# H2BR00.net
KiCad netlist of a schematic drawn in EAGLE
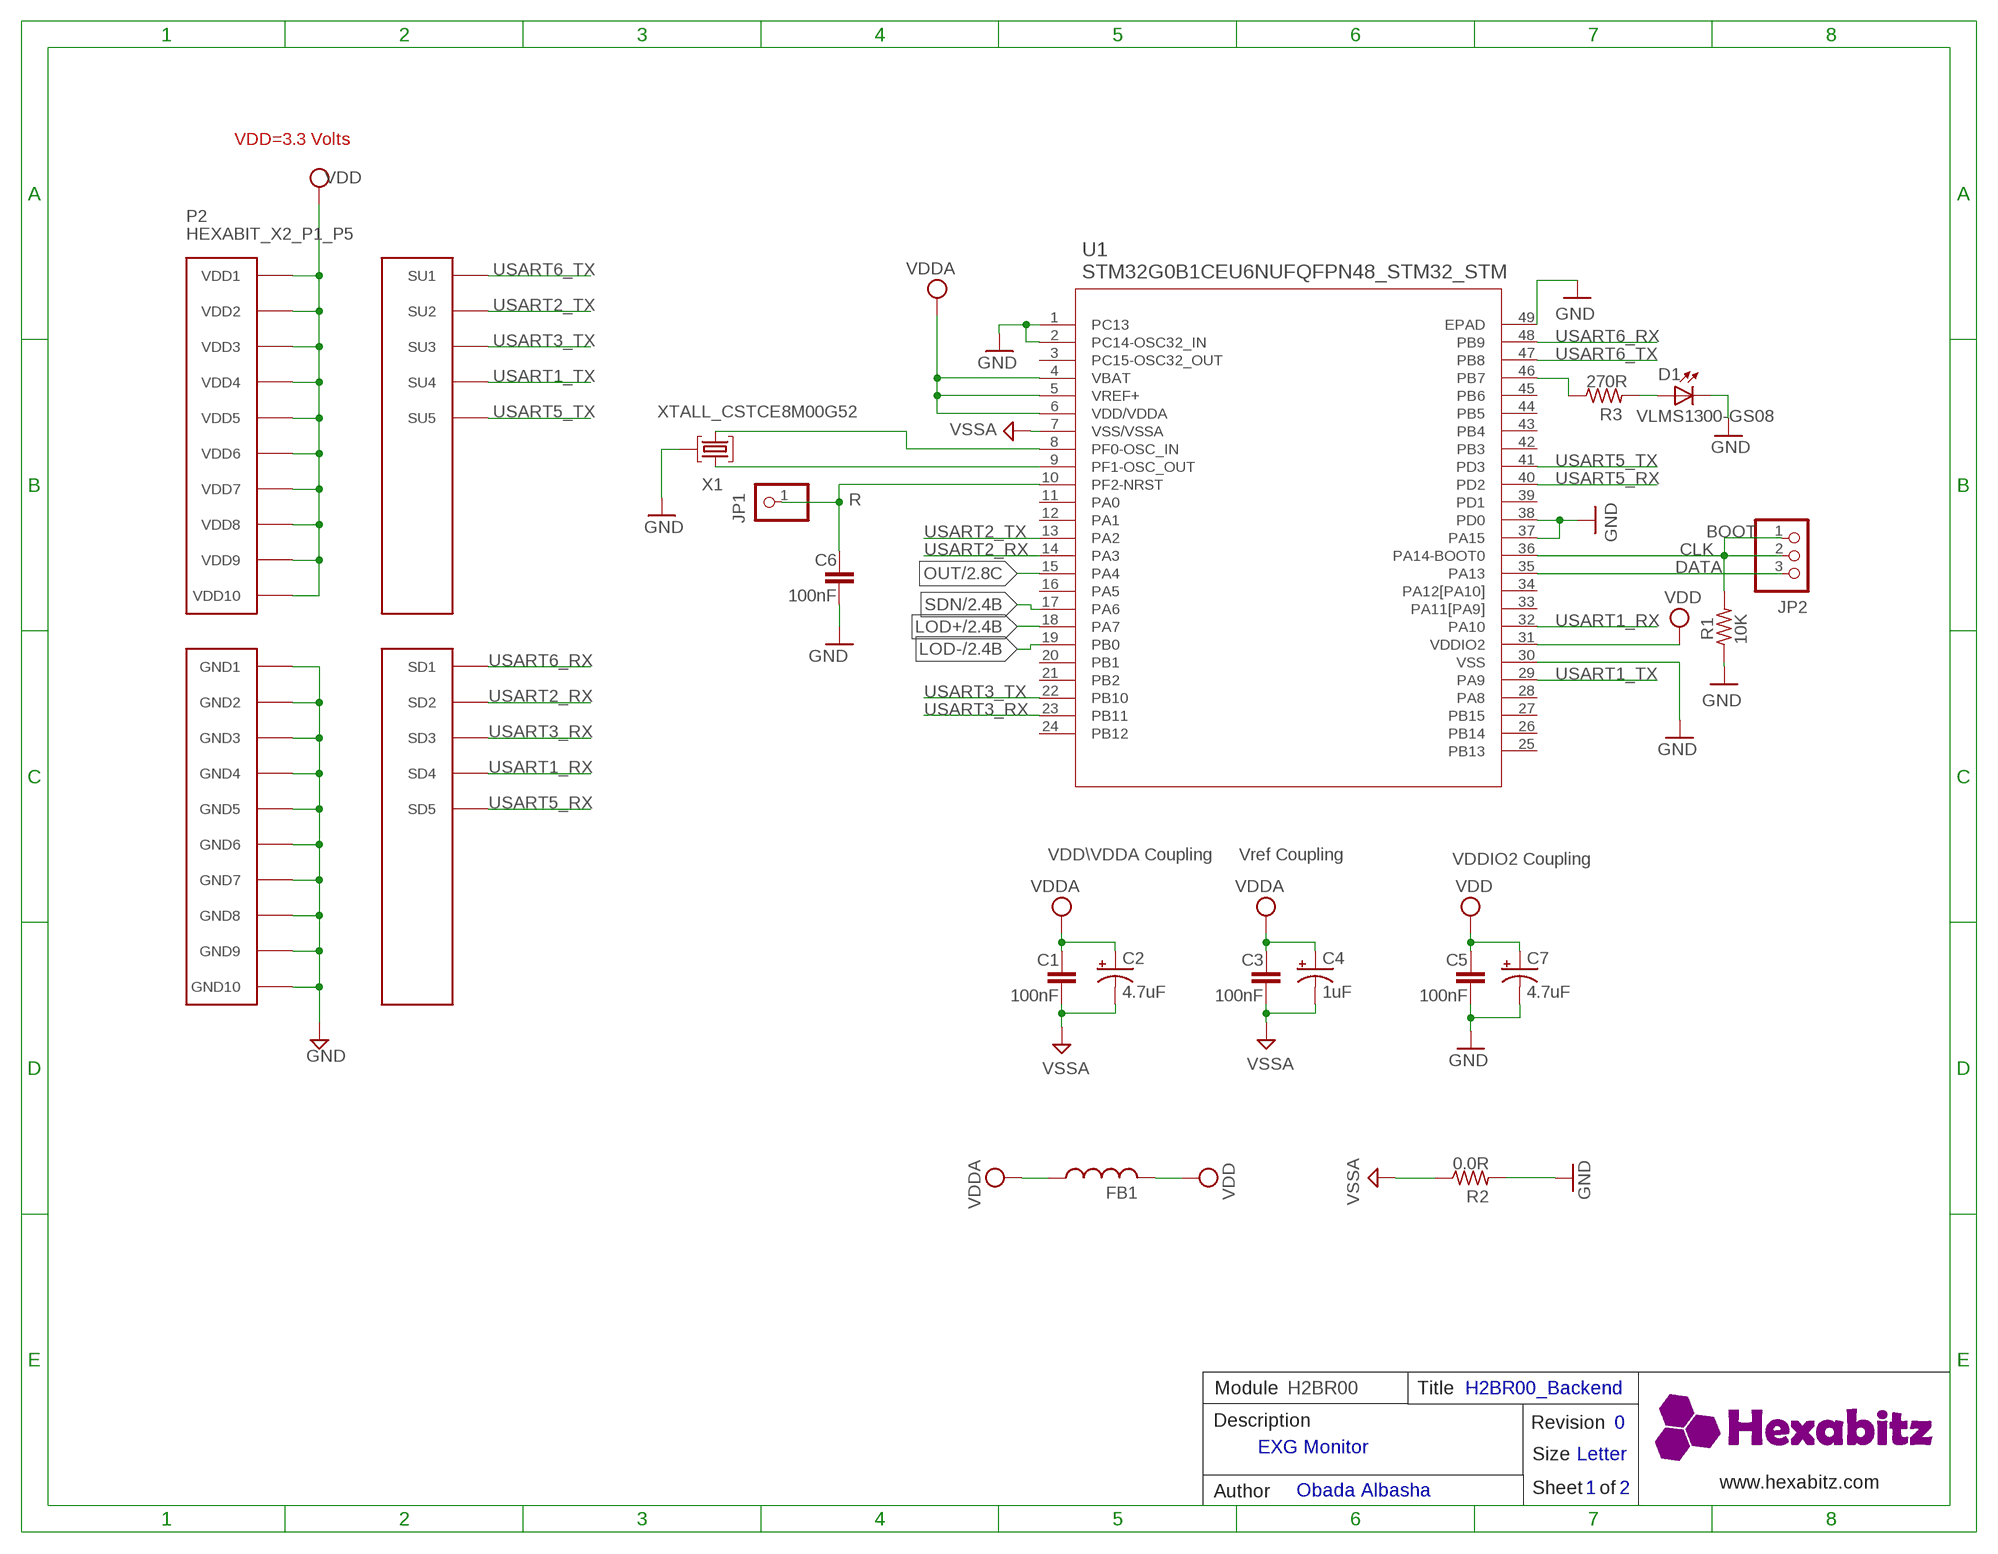
[diagram p0: schematic, sheet 1]
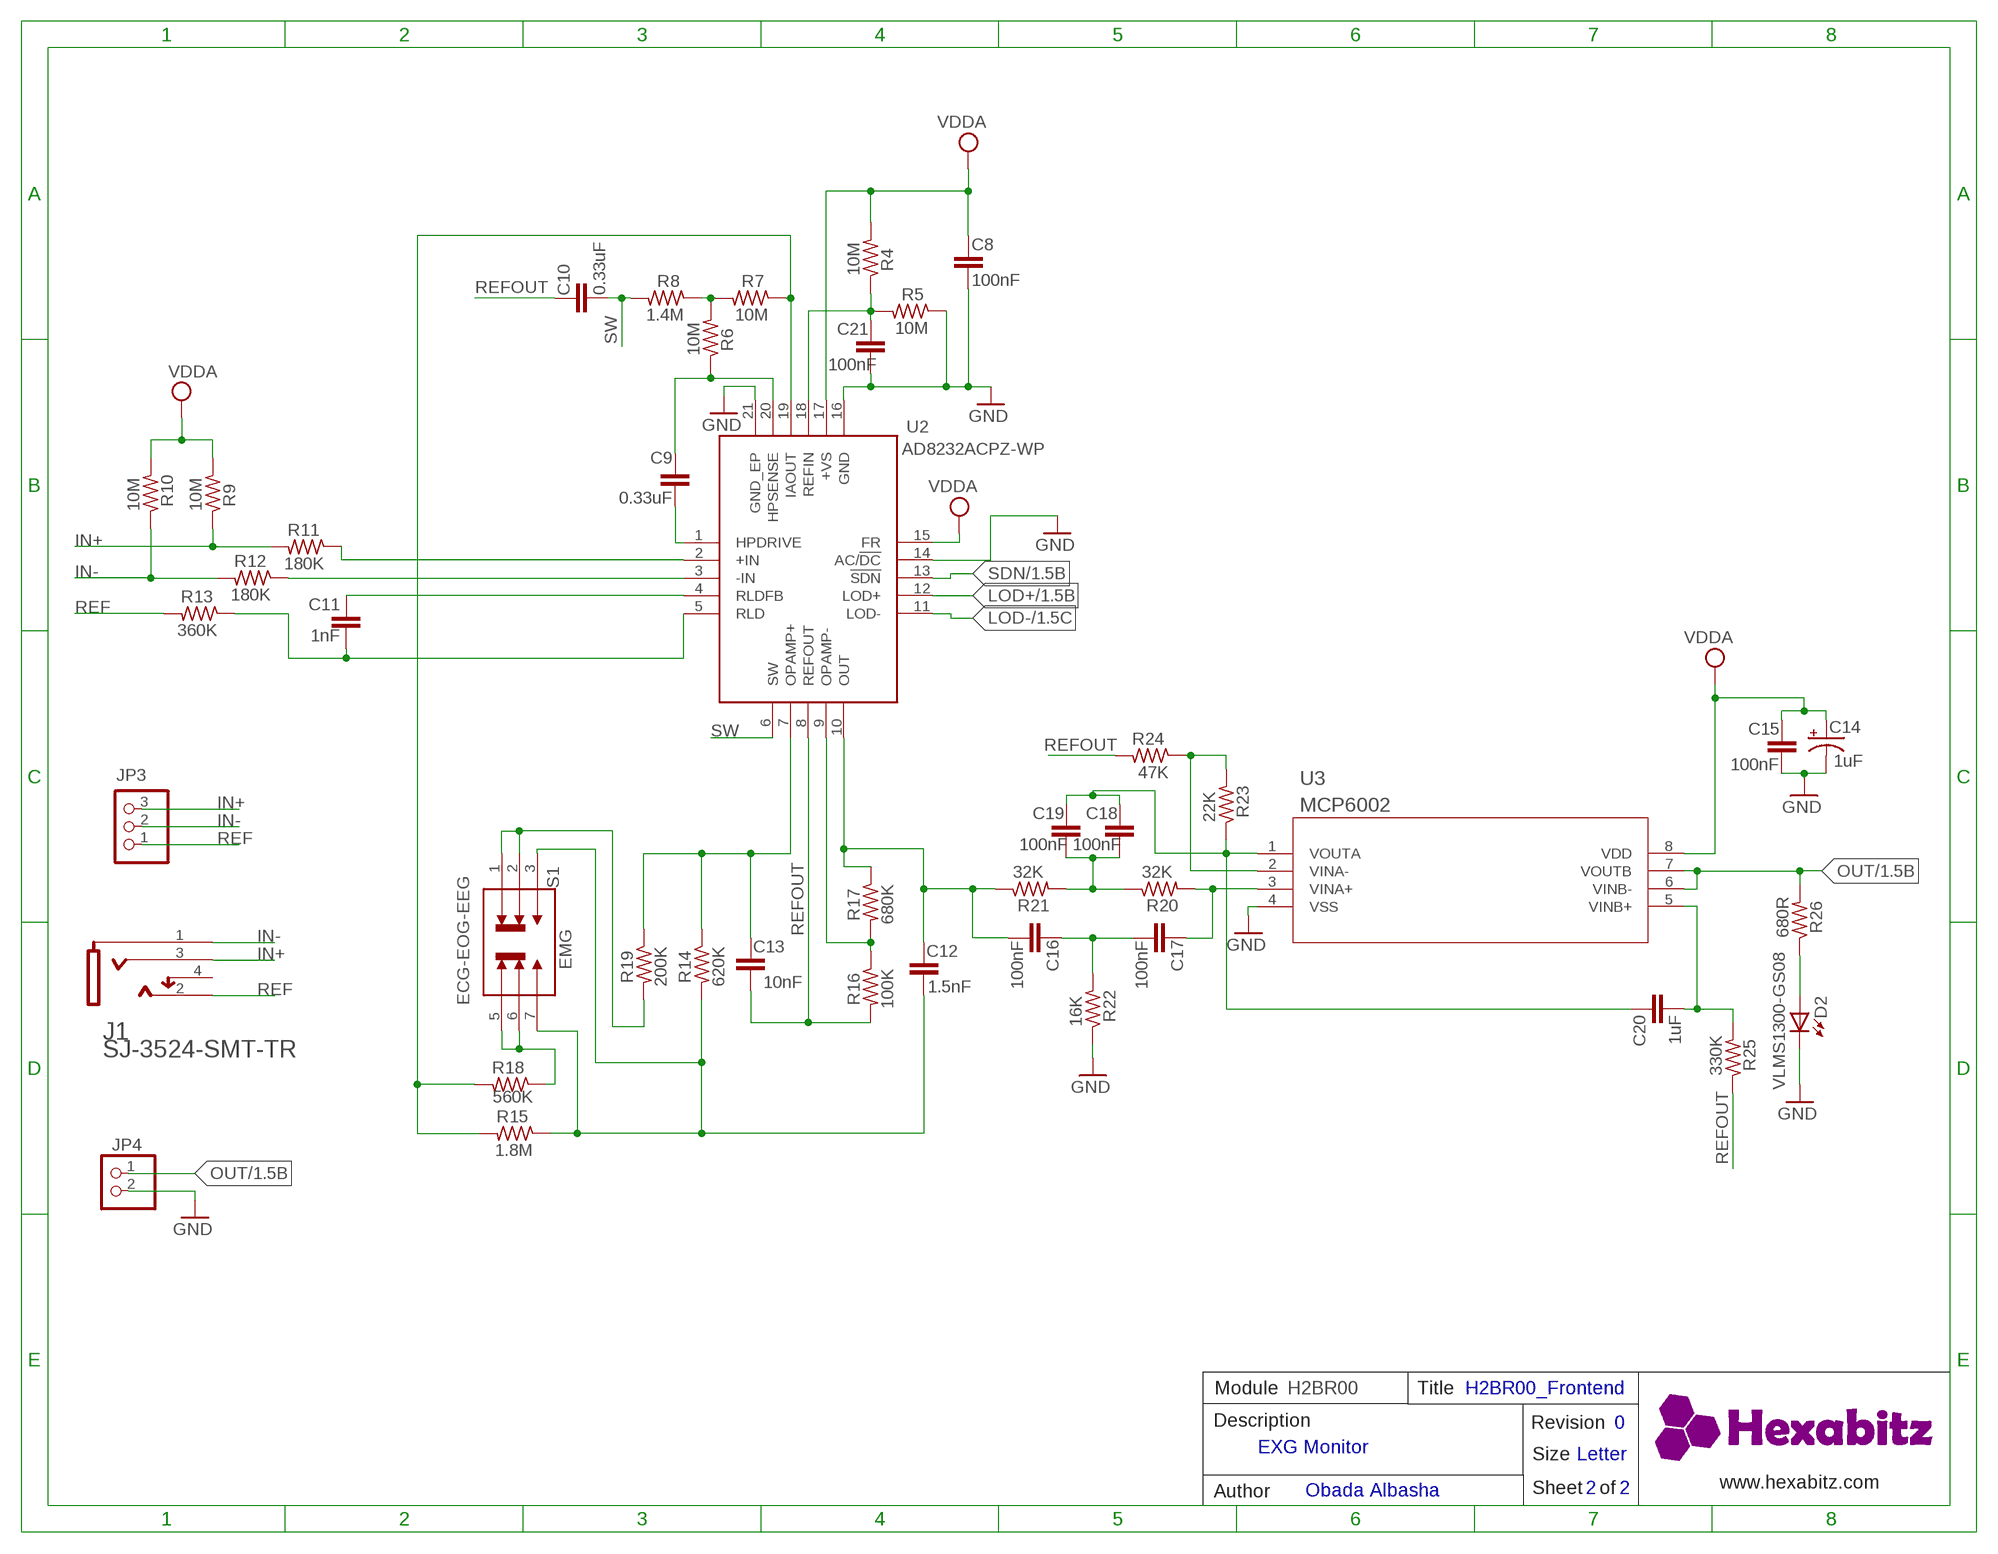
[diagram p1: schematic, sheet 2]

(export (version "E")
  (design (tool "Eeschema 10.0.6"))
  (components
    (comp (ref "C8")
      (value "100nF")
      (footprint "eagle-import:C-0603")
      (libsource (lib "eagle-import") (part "C-0603"))
    )
    (comp (ref "C9")
      (value "0.33uF")
      (footprint "eagle-import:C-0603")
      (libsource (lib "eagle-import") (part "C-0603"))
    )
    (comp (ref "C10")
      (value "0.33uF")
      (footprint "eagle-import:C-0603")
      (libsource (lib "eagle-import") (part "C-0603"))
    )
    (comp (ref "C11")
      (value "1nF")
      (footprint "eagle-import:C-0603")
      (libsource (lib "eagle-import") (part "C-0603"))
    )
    (comp (ref "C12")
      (value "1.5nF")
      (footprint "eagle-import:C-0603")
      (libsource (lib "eagle-import") (part "C-0603"))
    )
    (comp (ref "C13")
      (value "10nF")
      (footprint "eagle-import:C-0603")
      (libsource (lib "eagle-import") (part "C-0603"))
    )
    (comp (ref "C14")
      (value "1uF")
      (footprint "eagle-import:C-0805-POL")
      (libsource (lib "eagle-import") (part "C-0805-POL"))
    )
    (comp (ref "C15")
      (value "100nF")
      (footprint "eagle-import:C-0603")
      (libsource (lib "eagle-import") (part "C-0603"))
    )
    (comp (ref "C16")
      (value "100nF")
      (footprint "eagle-import:C-0603")
      (libsource (lib "eagle-import") (part "C-0603"))
    )
    (comp (ref "C17")
      (value "100nF")
      (footprint "eagle-import:C-0603")
      (libsource (lib "eagle-import") (part "C-0603"))
    )
    (comp (ref "C18")
      (value "100nF")
      (footprint "eagle-import:C-0603")
      (libsource (lib "eagle-import") (part "C-0603"))
    )
    (comp (ref "C19")
      (value "100nF")
      (footprint "eagle-import:C-0603")
      (libsource (lib "eagle-import") (part "C-0603"))
    )
    (comp (ref "C20")
      (value "1uF")
      (footprint "eagle-import:C-0603")
      (libsource (lib "eagle-import") (part "C-0603"))
    )
    (comp (ref "C21")
      (value "100nF")
      (footprint "eagle-import:C-0603")
      (libsource (lib "eagle-import") (part "C-0603"))
    )
    (comp (ref "D2")
      (value "VLMS1300-GS08")
      (footprint "eagle-import:VLMS1300-GS08")
      (fields
        (field (name "MFN") "Vishay")
        (field (name "MPN") "VLMS1300-GS08")
        (field (name "OCTOPART_URL") "https://octopart.com/vlms1300-gs08-vishay-21709201?r=sp&s=_gcP4_q8T1SC6PJQPTQ9yA")
      )
      (libsource (lib "eagle-import") (part "VLMS1300-GS08"))
    )
    (comp (ref "J1")
      (value "CUI_DEVICES_SJ-3524-SMT-TRCUI_DEVICES_SJ-3524-SMT-TR_0_0")
      (footprint "eagle-import:CUI_DEVICES_SJ-3524-SMT-TR_0")
      (fields
        (field (name "DIGIKEY_PART_NUMBER") "CP-3524SJCT-ND")
        (field (name "MOUSER_PART_NUMBER") "490-SJ-3524-SMT-TR")
        (field (name "MPN") "SJ-3524-SMT-TR")
      )
      (libsource (lib "eagle-import") (part "CUI_DEVICES_SJ-3524-SMT-TRCUI_DEVICES_SJ-3524-SMT-TR_0_0"))
    )
    (comp (ref "JP3")
      (value "PINHD-1X3")
      (footprint "eagle-import:1X03")
      (libsource (lib "eagle-import") (part "PINHD-1X3"))
    )
    (comp (ref "JP4")
      (value "PINHD-1X2(ROUND)")
      (footprint "eagle-import:1X02")
      (libsource (lib "eagle-import") (part "PINHD-1X2(ROUND)"))
    )
    (comp (ref "R4")
      (value "10M")
      (footprint "eagle-import:R-0603")
      (libsource (lib "eagle-import") (part "R-0603"))
    )
    (comp (ref "R5")
      (value "10M")
      (footprint "eagle-import:R-0603")
      (libsource (lib "eagle-import") (part "R-0603"))
    )
    (comp (ref "R6")
      (value "10M")
      (footprint "eagle-import:R-0603")
      (libsource (lib "eagle-import") (part "R-0603"))
    )
    (comp (ref "R7")
      (value "10M")
      (footprint "eagle-import:R-0603")
      (libsource (lib "eagle-import") (part "R-0603"))
    )
    (comp (ref "R8")
      (value "1.4M")
      (footprint "eagle-import:R-0603")
      (libsource (lib "eagle-import") (part "R-0603"))
    )
    (comp (ref "R9")
      (value "10M")
      (footprint "eagle-import:R-0603")
      (libsource (lib "eagle-import") (part "R-0603"))
    )
    (comp (ref "R10")
      (value "10M")
      (footprint "eagle-import:R-0603")
      (libsource (lib "eagle-import") (part "R-0603"))
    )
    (comp (ref "R11")
      (value "180K")
      (footprint "eagle-import:R-0603")
      (libsource (lib "eagle-import") (part "R-0603"))
    )
    (comp (ref "R12")
      (value "180K")
      (footprint "eagle-import:R-0603")
      (libsource (lib "eagle-import") (part "R-0603"))
    )
    (comp (ref "R13")
      (value "360K")
      (footprint "eagle-import:R-0603")
      (libsource (lib "eagle-import") (part "R-0603"))
    )
    (comp (ref "R14")
      (value "620K")
      (footprint "eagle-import:R-0603")
      (libsource (lib "eagle-import") (part "R-0603"))
    )
    (comp (ref "R15")
      (value "1.8M")
      (footprint "eagle-import:R-0603")
      (libsource (lib "eagle-import") (part "R-0603"))
    )
    (comp (ref "R16")
      (value "100K")
      (footprint "eagle-import:R-0603")
      (libsource (lib "eagle-import") (part "R-0603"))
    )
    (comp (ref "R17")
      (value "680K")
      (footprint "eagle-import:R-0603")
      (libsource (lib "eagle-import") (part "R-0603"))
    )
    (comp (ref "R18")
      (value "560K")
      (footprint "eagle-import:R-0603")
      (libsource (lib "eagle-import") (part "R-0603"))
    )
    (comp (ref "R19")
      (value "200K")
      (footprint "eagle-import:R-0603")
      (libsource (lib "eagle-import") (part "R-0603"))
    )
    (comp (ref "R20")
      (value "32K")
      (footprint "eagle-import:R-0603")
      (libsource (lib "eagle-import") (part "R-0603"))
    )
    (comp (ref "R21")
      (value "32K")
      (footprint "eagle-import:R-0603")
      (libsource (lib "eagle-import") (part "R-0603"))
    )
    (comp (ref "R22")
      (value "16K")
      (footprint "eagle-import:R-0603")
      (libsource (lib "eagle-import") (part "R-0603"))
    )
    (comp (ref "R23")
      (value "22K")
      (footprint "eagle-import:R-0603")
      (libsource (lib "eagle-import") (part "R-0603"))
    )
    (comp (ref "R24")
      (value "47K")
      (footprint "eagle-import:R-0603")
      (libsource (lib "eagle-import") (part "R-0603"))
    )
    (comp (ref "R25")
      (value "330K")
      (footprint "eagle-import:R-0603")
      (libsource (lib "eagle-import") (part "R-0603"))
    )
    (comp (ref "R26")
      (value "680R")
      (footprint "eagle-import:R-0603")
      (libsource (lib "eagle-import") (part "R-0603"))
    )
    (comp (ref "S1")
      (value "JS202011JCQN")
      (footprint "eagle-import:SW_JS202011JCQN")
      (fields (field (name "DIGI-KEY_PART_NUMBER") "CKN10723TR-ND") (field (name "MF") "C&K"))
      (libsource (lib "eagle-import") (part "JS202011JCQN"))
    )
    (comp (ref "U2")
      (value "AD8232ACPZ-WP")
      (footprint "eagle-import:QFN50P400X400X80-21N")
      (fields (field (name "MOUSER_PART_NUMBER") "584-AD8232ACPZ-WP"))
      (libsource (lib "eagle-import") (part "AD8232ACPZ-WP"))
    )
    (comp (ref "U3")
      (value "MCP6002")
      (footprint "eagle-import:SOIC8-N_MC_MCH-L")
      (fields
        (field (name "MANUFACTURER_PART_NUMBER") "MCP6002-I/SN")
        (field (name "COPYRIGHT") "Copyright (C) 2022 Ultra Librarian. All rights reserved.")
      )
      (libsource (lib "eagle-import") (part "MCP6002-I/SNSOIC8-N_MC_MCH-L"))
    )
    (comp (ref "C1")
      (value "100nF")
      (footprint "eagle-import:C-0603")
      (libsource (lib "eagle-import") (part "C-0603"))
    )
    (comp (ref "C2")
      (value "4.7uF")
      (footprint "eagle-import:C-0805-POL")
      (libsource (lib "eagle-import") (part "C-0805-POL"))
    )
    (comp (ref "C3")
      (value "100nF")
      (footprint "eagle-import:C-0603")
      (libsource (lib "eagle-import") (part "C-0603"))
    )
    (comp (ref "C4")
      (value "1uF")
      (footprint "eagle-import:C-0805-POL")
      (libsource (lib "eagle-import") (part "C-0805-POL"))
    )
    (comp (ref "C5")
      (value "100nF")
      (footprint "eagle-import:C-0603")
      (libsource (lib "eagle-import") (part "C-0603"))
    )
    (comp (ref "C6")
      (value "100nF")
      (footprint "eagle-import:C-0603")
      (libsource (lib "eagle-import") (part "C-0603"))
    )
    (comp (ref "C7")
      (value "4.7uF")
      (footprint "eagle-import:C-0805-POL")
      (libsource (lib "eagle-import") (part "C-0805-POL"))
    )
    (comp (ref "D1")
      (value "VLMS1300-GS08")
      (footprint "eagle-import:VLMS1300-GS08")
      (fields
        (field (name "MFN") "Vishay")
        (field (name "MPN") "VLMS1300-GS08")
        (field (name "OCTOPART_URL") "https://octopart.com/vlms1300-gs08-vishay-21709201?r=sp&s=_gcP4_q8T1SC6PJQPTQ9yA")
      )
      (libsource (lib "eagle-import") (part "VLMS1300-GS08"))
    )
    (comp (ref "FB1")
      (value "FB-0603")
      (footprint "eagle-import:FB-0603")
      (libsource (lib "eagle-import") (part "FB-0603"))
    )
    (comp (ref "JP1")
      (value "R")
      (footprint "eagle-import:1X01")
      (fields (field (name "MPN") "87227-1"))
      (libsource (lib "eagle-import") (part "PINHD-1X1"))
    )
    (comp (ref "JP2")
      (value "PINHD-1X3")
      (footprint "eagle-import:1X03")
      (libsource (lib "eagle-import") (part "PINHD-1X3"))
    )
    (comp (ref "P2")
      (value "HEXABIT_X2_P1_P5")
      (footprint "eagle-import:HEXABIT_17.32_X2_P1_P5")
      (libsource (lib "eagle-import") (part "HEXABIT_X2_P1_P5"))
    )
    (comp (ref "R1")
      (value "10K")
      (footprint "eagle-import:R-0603")
      (libsource (lib "eagle-import") (part "R-0603"))
    )
    (comp (ref "R2")
      (value "0.0R")
      (footprint "eagle-import:R-0603")
      (libsource (lib "eagle-import") (part "R-0603"))
    )
    (comp (ref "R3")
      (value "270R")
      (footprint "eagle-import:R-0603")
      (libsource (lib "eagle-import") (part "R-0603"))
    )
    (comp (ref "U1")
      (value "STM32G0B1CEU6NUFQFPN48_STM32_STM")
      (footprint "eagle-import:UFQFPN48_STM32_STM")
      (fields
        (field (name "MPN") "STM32G0B1CEU6N")
        (field (name "COPYRIGHT") "Copyright (C) 2022 Ultra Librarian. All rights reserved.")
      )
      (libsource (lib "eagle-import") (part "STM32G0B1CEU6NUFQFPN48_STM32_STM"))
    )
    (comp (ref "X1")
      (value "XTALL_CSTCE8M00G52")
      (footprint "eagle-import:XTALL_CSTCE8M00G52")
      (fields (field (name "MPN") "CSTCE8M00G52Z-R0"))
      (libsource (lib "eagle-import") (part "XTALL_CSTCE8M00G52"))
    )
  )
  (nets
    (net (code "1") (name "CLK") (class "Default")
      (node (ref "JP2") (pin "1") (pinfunction "1_1") (pintype "passive"))
      (node (ref "JP2") (pin "2") (pinfunction "2_2") (pintype "passive"))
      (node (ref "R1") (pin "2") (pinfunction "2_2") (pintype "passive"))
      (node (ref "U1") (pin "36") (pinfunction "PA14-BOOT0_36") (pintype "bidirectional"))
    )
    (net (code "2") (name "DATA") (class "Default")
      (node (ref "JP2") (pin "3") (pinfunction "3_3") (pintype "passive"))
      (node (ref "U1") (pin "35") (pinfunction "PA13_35") (pintype "bidirectional"))
    )
    (net (code "3") (name "GND") (class "Default")
      (node (ref "C14") (pin "2") (pinfunction "-_2") (pintype "passive"))
      (node (ref "C15") (pin "2") (pinfunction "2_2") (pintype "passive"))
      (node (ref "C21") (pin "2") (pinfunction "2_2") (pintype "passive"))
      (node (ref "C5") (pin "2") (pinfunction "2_2") (pintype "passive"))
      (node (ref "C6") (pin "2") (pinfunction "2_2") (pintype "passive"))
      (node (ref "C7") (pin "2") (pinfunction "-_2") (pintype "passive"))
      (node (ref "C8") (pin "2") (pinfunction "2_2") (pintype "passive"))
      (node (ref "D1") (pin "C") (pinfunction "C_C") (pintype "passive"))
      (node (ref "D2") (pin "C") (pinfunction "C_C") (pintype "passive"))
      (node (ref "JP4") (pin "2") (pinfunction "2_2") (pintype "passive"))
      (node (ref "P2") (pin "PAD_PD11") (pinfunction "GND1_PAD_PD11") (pintype "power_in"))
      (node (ref "P2") (pin "PAD_PD12") (pinfunction "GND2_PAD_PD12") (pintype "power_in"))
      (node (ref "P2") (pin "PAD_PD13") (pinfunction "GND3_PAD_PD13") (pintype "power_in"))
      (node (ref "P2") (pin "PAD_PD14") (pinfunction "GND4_PAD_PD14") (pintype "power_in"))
      (node (ref "P2") (pin "PAD_PD15") (pinfunction "GND5_PAD_PD15") (pintype "power_in"))
      (node (ref "P2") (pin "PAD_PD16") (pinfunction "GND6_PAD_PD16") (pintype "power_in"))
      (node (ref "P2") (pin "PAD_PD17") (pinfunction "GND7_PAD_PD17") (pintype "power_in"))
      (node (ref "P2") (pin "PAD_PD18") (pinfunction "GND8_PAD_PD18") (pintype "power_in"))
      (node (ref "P2") (pin "PAD_PD19") (pinfunction "GND9_PAD_PD19") (pintype "power_in"))
      (node (ref "P2") (pin "PAD_PD20") (pinfunction "GND10_PAD_PD20") (pintype "power_in"))
      (node (ref "R1") (pin "1") (pinfunction "1_1") (pintype "passive"))
      (node (ref "R2") (pin "2") (pinfunction "2_2") (pintype "passive"))
      (node (ref "R22") (pin "1") (pinfunction "1_1") (pintype "passive"))
      (node (ref "R5") (pin "1") (pinfunction "1_1") (pintype "passive"))
      (node (ref "U1") (pin "1") (pinfunction "PC13_1") (pintype "bidirectional"))
      (node (ref "U1") (pin "2") (pinfunction "PC14-OSC32_IN_2") (pintype "bidirectional"))
      (node (ref "U1") (pin "30") (pinfunction "VSS_30") (pintype "passive"))
      (node (ref "U1") (pin "37") (pinfunction "PA15_37") (pintype "bidirectional"))
      (node (ref "U1") (pin "38") (pinfunction "PD0_38") (pintype "bidirectional"))
      (node (ref "U1") (pin "49") (pinfunction "EPAD_49") (pintype "passive"))
      (node (ref "U2") (pin "14") (pinfunction "AC/~{DC}_14") (pintype "bidirectional"))
      (node (ref "U2") (pin "16") (pinfunction "GND_16") (pintype "power_in"))
      (node (ref "U2") (pin "21") (pinfunction "GND_EP_21") (pintype "power_in"))
      (node (ref "U3") (pin "4") (pinfunction "VSS_4") (pintype "passive"))
      (node (ref "X1") (pin "P$2") (pinfunction "2_P$2") (pintype "passive"))
    )
    (net (code "4") (name "IN+") (class "Default")
      (node (ref "J1") (pin "3") (pinfunction "RING_3") (pintype "passive"))
      (node (ref "JP3") (pin "3") (pinfunction "3_3") (pintype "passive"))
      (node (ref "R11") (pin "2") (pinfunction "2_2") (pintype "passive"))
      (node (ref "R9") (pin "1") (pinfunction "1_1") (pintype "passive"))
    )
    (net (code "5") (name "IN-") (class "Default")
      (node (ref "J1") (pin "1") (pinfunction "SLEEVE_1") (pintype "passive"))
      (node (ref "JP3") (pin "2") (pinfunction "2_2") (pintype "passive"))
      (node (ref "R10") (pin "1") (pinfunction "1_1") (pintype "passive"))
      (node (ref "R12") (pin "2") (pinfunction "2_2") (pintype "passive"))
    )
    (net (code "6") (name "LOD+") (class "Default")
      (node (ref "U1") (pin "18") (pinfunction "PA7_18") (pintype "bidirectional"))
      (node (ref "U2") (pin "12") (pinfunction "LOD+_12") (pintype "bidirectional"))
    )
    (net (code "7") (name "LOD-") (class "Default")
      (node (ref "U1") (pin "19") (pinfunction "PB0_19") (pintype "bidirectional"))
      (node (ref "U2") (pin "11") (pinfunction "LOD-_11") (pintype "bidirectional"))
    )
    (net (code "8") (name "Net-(C12-Pad2)") (class "Default")
      (node (ref "C12") (pin "2") (pinfunction "2_2") (pintype "passive"))
      (node (ref "R14") (pin "2") (pinfunction "2_2") (pintype "passive"))
      (node (ref "R15") (pin "1") (pinfunction "1_1") (pintype "passive"))
      (node (ref "S1") (pin "3") (pinfunction "3_3") (pintype "passive"))
      (node (ref "S1") (pin "7") (pinfunction "7_7") (pintype "passive"))
    )
    (net (code "9") (name "Net-(C16-Pad1)") (class "Default")
      (node (ref "C16") (pin "1") (pinfunction "1_1") (pintype "passive"))
      (node (ref "C17") (pin "2") (pinfunction "2_2") (pintype "passive"))
      (node (ref "R22") (pin "2") (pinfunction "2_2") (pintype "passive"))
    )
    (net (code "10") (name "Net-(C18-Pad2)") (class "Default")
      (node (ref "C18") (pin "2") (pinfunction "2_2") (pintype "passive"))
      (node (ref "C19") (pin "2") (pinfunction "2_2") (pintype "passive"))
      (node (ref "R20") (pin "1") (pinfunction "1_1") (pintype "passive"))
      (node (ref "R21") (pin "2") (pinfunction "2_2") (pintype "passive"))
    )
    (net (code "11") (name "Net-(D1-PadA)") (class "Default")
      (node (ref "D1") (pin "A") (pinfunction "A_A") (pintype "passive"))
      (node (ref "R3") (pin "2") (pinfunction "2_2") (pintype "passive"))
    )
    (net (code "12") (name "Net-(D2-PadA)") (class "Default")
      (node (ref "D2") (pin "A") (pinfunction "A_A") (pintype "passive"))
      (node (ref "R26") (pin "1") (pinfunction "1_1") (pintype "passive"))
    )
    (net (code "13") (name "Net-(R6-Pad2)") (class "Default")
      (node (ref "R6") (pin "2") (pinfunction "2_2") (pintype "passive"))
      (node (ref "R7") (pin "2") (pinfunction "2_2") (pintype "passive"))
      (node (ref "R8") (pin "1") (pinfunction "1_1") (pintype "passive"))
    )
    (net (code "14") (name "Net-(R18-Pad1)") (class "Default")
      (node (ref "R18") (pin "1") (pinfunction "1_1") (pintype "passive"))
      (node (ref "S1") (pin "5") (pinfunction "5_5") (pintype "passive"))
      (node (ref "S1") (pin "6") (pinfunction "6_6") (pintype "passive"))
    )
    (net (code "15") (name "Net-(R19-Pad2)") (class "Default")
      (node (ref "R19") (pin "2") (pinfunction "2_2") (pintype "passive"))
      (node (ref "S1") (pin "1") (pinfunction "1_1") (pintype "passive"))
      (node (ref "S1") (pin "2") (pinfunction "2_2") (pintype "passive"))
    )
    (net (code "16") (name "Net-(U1-PB7)") (class "Default")
      (node (ref "R3") (pin "1") (pinfunction "1_1") (pintype "passive"))
      (node (ref "U1") (pin "46") (pinfunction "PB7_46") (pintype "bidirectional"))
    )
    (net (code "17") (name "Net-(U1-PF0-OSC_IN)") (class "Default")
      (node (ref "U1") (pin "8") (pinfunction "PF0-OSC_IN_8") (pintype "bidirectional"))
      (node (ref "X1") (pin "P$3") (pinfunction "3_P$3") (pintype "passive"))
    )
    (net (code "18") (name "Net-(U1-PF1-OSC_OUT)") (class "Default")
      (node (ref "U1") (pin "9") (pinfunction "PF1-OSC_OUT_9") (pintype "bidirectional"))
      (node (ref "X1") (pin "P$1") (pinfunction "1_P$1") (pintype "passive"))
    )
    (net (code "19") (name "Net-(U1-PF2-NRST)") (class "Default")
      (node (ref "C6") (pin "1") (pinfunction "1_1") (pintype "passive"))
      (node (ref "JP1") (pin "1") (pinfunction "1_1") (pintype "passive"))
      (node (ref "U1") (pin "10") (pinfunction "PF2-NRST_10") (pintype "bidirectional"))
    )
    (net (code "20") (name "Net-(U2-+IN)") (class "Default")
      (node (ref "R11") (pin "1") (pinfunction "1_1") (pintype "passive"))
      (node (ref "U2") (pin "2") (pinfunction "+IN_2") (pintype "input"))
    )
    (net (code "21") (name "Net-(U2--IN)") (class "Default")
      (node (ref "R12") (pin "1") (pinfunction "1_1") (pintype "passive"))
      (node (ref "U2") (pin "3") (pinfunction "-IN_3") (pintype "input"))
    )
    (net (code "22") (name "Net-(U2-HPDRIVE)") (class "Default")
      (node (ref "C9") (pin "2") (pinfunction "2_2") (pintype "passive"))
      (node (ref "U2") (pin "1") (pinfunction "HPDRIVE_1") (pintype "bidirectional"))
    )
    (net (code "23") (name "Net-(U2-HPSENSE)") (class "Default")
      (node (ref "C9") (pin "1") (pinfunction "1_1") (pintype "passive"))
      (node (ref "R6") (pin "1") (pinfunction "1_1") (pintype "passive"))
      (node (ref "U2") (pin "20") (pinfunction "HPSENSE_20") (pintype "bidirectional"))
    )
    (net (code "24") (name "Net-(U2-IAOUT)") (class "Default")
      (node (ref "R15") (pin "2") (pinfunction "2_2") (pintype "passive"))
      (node (ref "R18") (pin "2") (pinfunction "2_2") (pintype "passive"))
      (node (ref "R7") (pin "1") (pinfunction "1_1") (pintype "passive"))
      (node (ref "U2") (pin "19") (pinfunction "IAOUT_19") (pintype "output"))
    )
    (net (code "25") (name "Net-(U2-OPAMP+)") (class "Default")
      (node (ref "C13") (pin "1") (pinfunction "1_1") (pintype "passive"))
      (node (ref "R14") (pin "1") (pinfunction "1_1") (pintype "passive"))
      (node (ref "R19") (pin "1") (pinfunction "1_1") (pintype "passive"))
      (node (ref "U2") (pin "7") (pinfunction "OPAMP+_7") (pintype "bidirectional"))
    )
    (net (code "26") (name "Net-(U2-OPAMP-)") (class "Default")
      (node (ref "R16") (pin "1") (pinfunction "1_1") (pintype "passive"))
      (node (ref "R17") (pin "2") (pinfunction "2_2") (pintype "passive"))
      (node (ref "U2") (pin "9") (pinfunction "OPAMP-_9") (pintype "bidirectional"))
    )
    (net (code "27") (name "Net-(U2-OUT)") (class "Default")
      (node (ref "C12") (pin "1") (pinfunction "1_1") (pintype "passive"))
      (node (ref "C16") (pin "2") (pinfunction "2_2") (pintype "passive"))
      (node (ref "R17") (pin "1") (pinfunction "1_1") (pintype "passive"))
      (node (ref "R21") (pin "1") (pinfunction "1_1") (pintype "passive"))
      (node (ref "U2") (pin "10") (pinfunction "OUT_10") (pintype "output"))
    )
    (net (code "28") (name "Net-(U2-REFIN)") (class "Default")
      (node (ref "C21") (pin "1") (pinfunction "1_1") (pintype "passive"))
      (node (ref "R4") (pin "1") (pinfunction "1_1") (pintype "passive"))
      (node (ref "R5") (pin "2") (pinfunction "2_2") (pintype "passive"))
      (node (ref "U2") (pin "18") (pinfunction "REFIN_18") (pintype "input"))
    )
    (net (code "29") (name "Net-(U2-RLD)") (class "Default")
      (node (ref "C11") (pin "2") (pinfunction "2_2") (pintype "passive"))
      (node (ref "R13") (pin "1") (pinfunction "1_1") (pintype "passive"))
      (node (ref "U2") (pin "5") (pinfunction "RLD_5") (pintype "bidirectional"))
    )
    (net (code "30") (name "Net-(U2-RLDFB)") (class "Default")
      (node (ref "C11") (pin "1") (pinfunction "1_1") (pintype "passive"))
      (node (ref "U2") (pin "4") (pinfunction "RLDFB_4") (pintype "bidirectional"))
    )
    (net (code "31") (name "Net-(U3-VINA+)") (class "Default")
      (node (ref "C17") (pin "1") (pinfunction "1_1") (pintype "passive"))
      (node (ref "R20") (pin "2") (pinfunction "2_2") (pintype "passive"))
      (node (ref "U3") (pin "3") (pinfunction "VINA+_3") (pintype "input"))
    )
    (net (code "32") (name "Net-(U3-VINA-)") (class "Default")
      (node (ref "R23") (pin "2") (pinfunction "2_2") (pintype "passive"))
      (node (ref "R24") (pin "1") (pinfunction "1_1") (pintype "passive"))
      (node (ref "U3") (pin "2") (pinfunction "VINA-_2") (pintype "input"))
    )
    (net (code "33") (name "Net-(U3-VINB+)") (class "Default")
      (node (ref "C20") (pin "2") (pinfunction "2_2") (pintype "passive"))
      (node (ref "R25") (pin "2") (pinfunction "2_2") (pintype "passive"))
      (node (ref "U3") (pin "5") (pinfunction "VINB+_5") (pintype "input"))
    )
    (net (code "34") (name "Net-(U3-VOUTA)") (class "Default")
      (node (ref "C18") (pin "1") (pinfunction "1_1") (pintype "passive"))
      (node (ref "C19") (pin "1") (pinfunction "1_1") (pintype "passive"))
      (node (ref "C20") (pin "1") (pinfunction "1_1") (pintype "passive"))
      (node (ref "R23") (pin "1") (pinfunction "1_1") (pintype "passive"))
      (node (ref "U3") (pin "1") (pinfunction "VOUTA_1") (pintype "output"))
    )
    (net (code "35") (name "OUT") (class "Default")
      (node (ref "JP4") (pin "1") (pinfunction "1_1") (pintype "passive"))
      (node (ref "R26") (pin "2") (pinfunction "2_2") (pintype "passive"))
      (node (ref "U1") (pin "15") (pinfunction "PA4_15") (pintype "bidirectional"))
      (node (ref "U3") (pin "6") (pinfunction "VINB-_6") (pintype "input"))
      (node (ref "U3") (pin "7") (pinfunction "VOUTB_7") (pintype "output"))
    )
    (net (code "36") (name "REF") (class "Default")
      (node (ref "J1") (pin "2") (pinfunction "TIP_2") (pintype "passive"))
      (node (ref "JP3") (pin "1") (pinfunction "1_1") (pintype "passive"))
      (node (ref "R13") (pin "2") (pinfunction "2_2") (pintype "passive"))
    )
    (net (code "37") (name "REFOUT") (class "Default")
      (node (ref "C10") (pin "1") (pinfunction "1_1") (pintype "passive"))
      (node (ref "C13") (pin "2") (pinfunction "2_2") (pintype "passive"))
      (node (ref "R16") (pin "2") (pinfunction "2_2") (pintype "passive"))
      (node (ref "R24") (pin "2") (pinfunction "2_2") (pintype "passive"))
      (node (ref "R25") (pin "1") (pinfunction "1_1") (pintype "passive"))
      (node (ref "U2") (pin "8") (pinfunction "REFOUT_8") (pintype "output"))
    )
    (net (code "38") (name "SDN") (class "Default")
      (node (ref "U1") (pin "17") (pinfunction "PA6_17") (pintype "bidirectional"))
      (node (ref "U2") (pin "13") (pinfunction "~{SDN}_13") (pintype "bidirectional"))
    )
    (net (code "39") (name "SW") (class "Default")
      (node (ref "C10") (pin "2") (pinfunction "2_2") (pintype "passive"))
      (node (ref "R8") (pin "2") (pinfunction "2_2") (pintype "passive"))
      (node (ref "U2") (pin "6") (pinfunction "SW_6") (pintype "bidirectional"))
    )
    (net (code "40") (name "USART1_RX") (class "Default")
      (node (ref "P2") (pin "PAD_PD4") (pinfunction "SD4_PAD_PD4") (pintype "bidirectional"))
      (node (ref "U1") (pin "32") (pinfunction "PA10_32") (pintype "bidirectional"))
    )
    (net (code "41") (name "USART1_TX") (class "Default")
      (node (ref "P2") (pin "PAD_PU4") (pinfunction "SU4_PAD_PU4") (pintype "bidirectional"))
      (node (ref "U1") (pin "29") (pinfunction "PA9_29") (pintype "bidirectional"))
    )
    (net (code "42") (name "USART2_RX") (class "Default")
      (node (ref "P2") (pin "PAD_PD2") (pinfunction "SD2_PAD_PD2") (pintype "bidirectional"))
      (node (ref "U1") (pin "14") (pinfunction "PA3_14") (pintype "bidirectional"))
    )
    (net (code "43") (name "USART2_TX") (class "Default")
      (node (ref "P2") (pin "PAD_PU2") (pinfunction "SU2_PAD_PU2") (pintype "bidirectional"))
      (node (ref "U1") (pin "13") (pinfunction "PA2_13") (pintype "bidirectional"))
    )
    (net (code "44") (name "USART3_RX") (class "Default")
      (node (ref "P2") (pin "PAD_PD3") (pinfunction "SD3_PAD_PD3") (pintype "bidirectional"))
      (node (ref "U1") (pin "23") (pinfunction "PB11_23") (pintype "bidirectional"))
    )
    (net (code "45") (name "USART3_TX") (class "Default")
      (node (ref "P2") (pin "PAD_PU3") (pinfunction "SU3_PAD_PU3") (pintype "bidirectional"))
      (node (ref "U1") (pin "22") (pinfunction "PB10_22") (pintype "bidirectional"))
    )
    (net (code "46") (name "USART5_RX") (class "Default")
      (node (ref "P2") (pin "PAD_PD5") (pinfunction "SD5_PAD_PD5") (pintype "bidirectional"))
      (node (ref "U1") (pin "40") (pinfunction "PD2_40") (pintype "bidirectional"))
    )
    (net (code "47") (name "USART5_TX") (class "Default")
      (node (ref "P2") (pin "PAD_PU5") (pinfunction "SU5_PAD_PU5") (pintype "bidirectional"))
      (node (ref "U1") (pin "41") (pinfunction "PD3_41") (pintype "bidirectional"))
    )
    (net (code "48") (name "USART6_RX") (class "Default")
      (node (ref "P2") (pin "PAD_PD1") (pinfunction "SD1_PAD_PD1") (pintype "bidirectional"))
      (node (ref "U1") (pin "48") (pinfunction "PB9_48") (pintype "bidirectional"))
    )
    (net (code "49") (name "USART6_TX") (class "Default")
      (node (ref "P2") (pin "PAD_PU1") (pinfunction "SU1_PAD_PU1") (pintype "bidirectional"))
      (node (ref "U1") (pin "47") (pinfunction "PB8_47") (pintype "bidirectional"))
    )
    (net (code "50") (name "VDD") (class "Default")
      (node (ref "C5") (pin "1") (pinfunction "1_1") (pintype "passive"))
      (node (ref "C7") (pin "1") (pinfunction "+_1") (pintype "passive"))
      (node (ref "FB1") (pin "2") (pinfunction "2_2") (pintype "passive"))
      (node (ref "P2") (pin "PAD_PU11") (pinfunction "VDD1_PAD_PU11") (pintype "power_in"))
      (node (ref "P2") (pin "PAD_PU12") (pinfunction "VDD2_PAD_PU12") (pintype "power_in"))
      (node (ref "P2") (pin "PAD_PU13") (pinfunction "VDD3_PAD_PU13") (pintype "power_in"))
      (node (ref "P2") (pin "PAD_PU14") (pinfunction "VDD4_PAD_PU14") (pintype "power_in"))
      (node (ref "P2") (pin "PAD_PU15") (pinfunction "VDD5_PAD_PU15") (pintype "power_in"))
      (node (ref "P2") (pin "PAD_PU16") (pinfunction "VDD6_PAD_PU16") (pintype "power_in"))
      (node (ref "P2") (pin "PAD_PU17") (pinfunction "VDD7_PAD_PU17") (pintype "power_in"))
      (node (ref "P2") (pin "PAD_PU18") (pinfunction "VDD8_PAD_PU18") (pintype "power_in"))
      (node (ref "P2") (pin "PAD_PU19") (pinfunction "VDD9_PAD_PU19") (pintype "power_in"))
      (node (ref "P2") (pin "PAD_PU20") (pinfunction "VDD10_PAD_PU20") (pintype "power_in"))
      (node (ref "U1") (pin "31") (pinfunction "VDDIO2_31") (pintype "power_in"))
    )
    (net (code "51") (name "VDDA") (class "Default")
      (node (ref "C1") (pin "1") (pinfunction "1_1") (pintype "passive"))
      (node (ref "C14") (pin "1") (pinfunction "+_1") (pintype "passive"))
      (node (ref "C15") (pin "1") (pinfunction "1_1") (pintype "passive"))
      (node (ref "C2") (pin "1") (pinfunction "+_1") (pintype "passive"))
      (node (ref "C3") (pin "1") (pinfunction "1_1") (pintype "passive"))
      (node (ref "C4") (pin "1") (pinfunction "+_1") (pintype "passive"))
      (node (ref "C8") (pin "1") (pinfunction "1_1") (pintype "passive"))
      (node (ref "FB1") (pin "1") (pinfunction "1_1") (pintype "passive"))
      (node (ref "R10") (pin "2") (pinfunction "2_2") (pintype "passive"))
      (node (ref "R4") (pin "2") (pinfunction "2_2") (pintype "passive"))
      (node (ref "R9") (pin "2") (pinfunction "2_2") (pintype "passive"))
      (node (ref "U1") (pin "4") (pinfunction "VBAT_4") (pintype "power_in"))
      (node (ref "U1") (pin "5") (pinfunction "VREF+_5") (pintype "power_in"))
      (node (ref "U1") (pin "6") (pinfunction "VDD/VDDA_6") (pintype "power_in"))
      (node (ref "U2") (pin "15") (pinfunction "FR_15") (pintype "bidirectional"))
      (node (ref "U2") (pin "17") (pinfunction "+VS_17") (pintype "bidirectional"))
      (node (ref "U3") (pin "8") (pinfunction "VDD_8") (pintype "passive"))
    )
    (net (code "52") (name "VSSA") (class "Default")
      (node (ref "C1") (pin "2") (pinfunction "2_2") (pintype "passive"))
      (node (ref "C2") (pin "2") (pinfunction "-_2") (pintype "passive"))
      (node (ref "C3") (pin "2") (pinfunction "2_2") (pintype "passive"))
      (node (ref "C4") (pin "2") (pinfunction "-_2") (pintype "passive"))
      (node (ref "R2") (pin "1") (pinfunction "1_1") (pintype "passive"))
      (node (ref "U1") (pin "7") (pinfunction "VSS/VSSA_7") (pintype "passive"))
    )
    (net (code "53") (name "unconnected-(J1-TIP_SWITCH-Pad4)") (class "Default")
      (node (ref "J1") (pin "4") (pinfunction "TIP_SWITCH_4") (pintype "passive"))
    )
    (net (code "54") (name "unconnected-(U1-PA0-Pad11)") (class "Default")
      (node (ref "U1") (pin "11") (pinfunction "PA0_11") (pintype "bidirectional"))
    )
    (net (code "55") (name "unconnected-(U1-PA1-Pad12)") (class "Default")
      (node (ref "U1") (pin "12") (pinfunction "PA1_12") (pintype "bidirectional"))
    )
    (net (code "56") (name "unconnected-(U1-PA5-Pad16)") (class "Default")
      (node (ref "U1") (pin "16") (pinfunction "PA5_16") (pintype "bidirectional"))
    )
    (net (code "57") (name "unconnected-(U1-PA8-Pad28)") (class "Default")
      (node (ref "U1") (pin "28") (pinfunction "PA8_28") (pintype "bidirectional"))
    )
    (net (code "58") (name "unconnected-(U1-PA11[PA9]-Pad33)") (class "Default")
      (node (ref "U1") (pin "33") (pinfunction "PA11[PA9]_33") (pintype "bidirectional"))
    )
    (net (code "59") (name "unconnected-(U1-PA12[PA10]-Pad34)") (class "Default")
      (node (ref "U1") (pin "34") (pinfunction "PA12[PA10]_34") (pintype "bidirectional"))
    )
    (net (code "60") (name "unconnected-(U1-PB1-Pad20)") (class "Default")
      (node (ref "U1") (pin "20") (pinfunction "PB1_20") (pintype "bidirectional"))
    )
    (net (code "61") (name "unconnected-(U1-PB2-Pad21)") (class "Default")
      (node (ref "U1") (pin "21") (pinfunction "PB2_21") (pintype "bidirectional"))
    )
    (net (code "62") (name "unconnected-(U1-PB3-Pad42)") (class "Default")
      (node (ref "U1") (pin "42") (pinfunction "PB3_42") (pintype "bidirectional"))
    )
    (net (code "63") (name "unconnected-(U1-PB4-Pad43)") (class "Default")
      (node (ref "U1") (pin "43") (pinfunction "PB4_43") (pintype "bidirectional"))
    )
    (net (code "64") (name "unconnected-(U1-PB5-Pad44)") (class "Default")
      (node (ref "U1") (pin "44") (pinfunction "PB5_44") (pintype "bidirectional"))
    )
    (net (code "65") (name "unconnected-(U1-PB6-Pad45)") (class "Default")
      (node (ref "U1") (pin "45") (pinfunction "PB6_45") (pintype "bidirectional"))
    )
    (net (code "66") (name "unconnected-(U1-PB12-Pad24)") (class "Default")
      (node (ref "U1") (pin "24") (pinfunction "PB12_24") (pintype "bidirectional"))
    )
    (net (code "67") (name "unconnected-(U1-PB13-Pad25)") (class "Default")
      (node (ref "U1") (pin "25") (pinfunction "PB13_25") (pintype "bidirectional"))
    )
    (net (code "68") (name "unconnected-(U1-PB14-Pad26)") (class "Default")
      (node (ref "U1") (pin "26") (pinfunction "PB14_26") (pintype "bidirectional"))
    )
    (net (code "69") (name "unconnected-(U1-PB15-Pad27)") (class "Default")
      (node (ref "U1") (pin "27") (pinfunction "PB15_27") (pintype "bidirectional"))
    )
    (net (code "70") (name "unconnected-(U1-PC15-OSC32_OUT-Pad3)") (class "Default")
      (node (ref "U1") (pin "3") (pinfunction "PC15-OSC32_OUT_3") (pintype "bidirectional"))
    )
    (net (code "71") (name "unconnected-(U1-PD1-Pad39)") (class "Default")
      (node (ref "U1") (pin "39") (pinfunction "PD1_39") (pintype "bidirectional"))
    )
  )
)
